# OMS_cup_wash_sucction.net
KiCad netlist of a schematic drawn in EAGLE
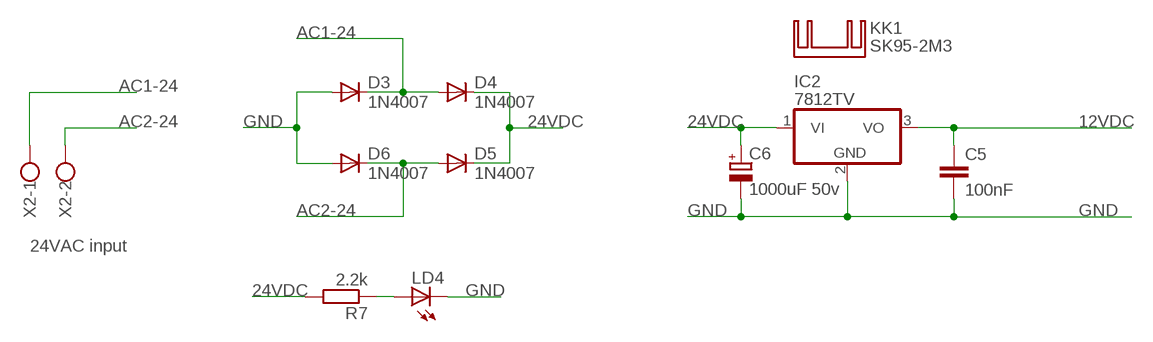
[diagram p0: schematic, sheet 1]
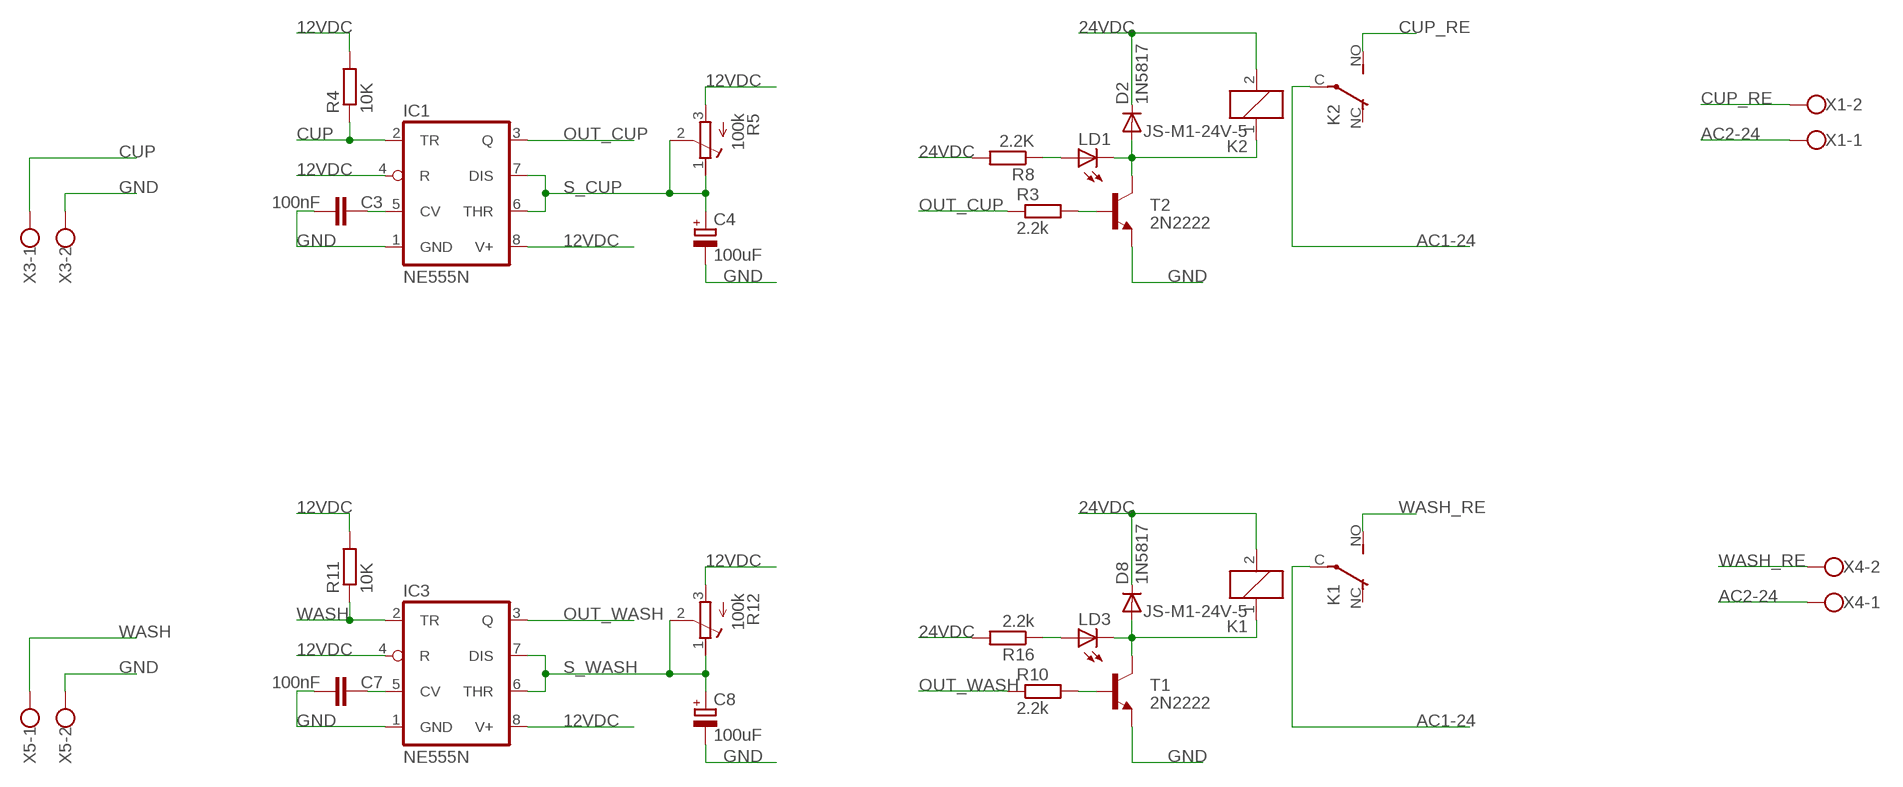
[diagram p1: schematic, sheet 2]
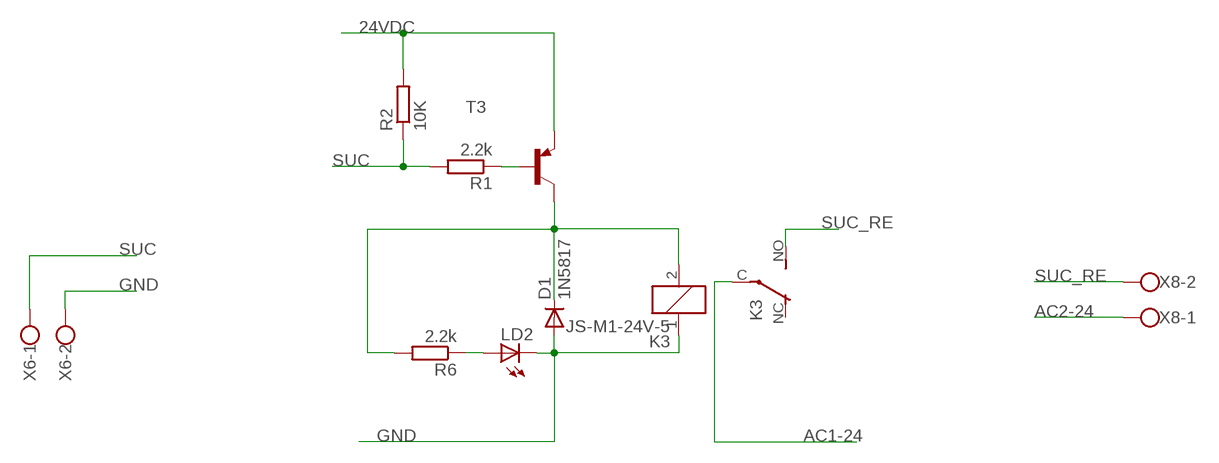
[diagram p2: schematic, sheet 3]

(export (version "E")
  (design (tool "Eeschema 10.0.6"))
  (components
    (comp (ref "D1")
      (value "1N5817")
      (footprint "eagle-import:DO41-10")
      (libsource (lib "eagle-import") (part "1N4004"))
    )
    (comp (ref "K3")
      (value "JS-M1-24V-5")
      (footprint "eagle-import:JS-M")
      (fields (field (name "MF") "FARNELL") (field (name "MPN") "JSM1-12V-5"))
      (libsource (lib "eagle-import") (part "JS-M1-12V-5"))
    )
    (comp (ref "LD2")
      (value "LED5MM")
      (footprint "eagle-import:LED5MM")
      (libsource (lib "eagle-import") (part "LED5MM"))
    )
    (comp (ref "R1")
      (value "2.2k")
      (footprint "eagle-import:0207_10")
      (libsource (lib "eagle-import") (part "R-EU_0207/10"))
    )
    (comp (ref "R2")
      (value "10K")
      (footprint "eagle-import:0207_10")
      (libsource (lib "eagle-import") (part "R-EU_0207/10"))
    )
    (comp (ref "R6")
      (value "2.2k")
      (footprint "eagle-import:0207_10")
      (libsource (lib "eagle-import") (part "R-EU_0207/10"))
    )
    (comp (ref "T3")
      (value "2N5401-PNP-TO92-EBC")
      (footprint "eagle-import:TO92-EBC")
      (libsource (lib "eagle-import") (part "-PNP-TO92-EBC2N5401"))
    )
    (comp (ref "X6")
      (value "W237-102")
      (footprint "eagle-import:W237-102")
      (libsource (lib "eagle-import") (part "W237-102"))
    )
    (comp (ref "X8")
      (value "W237-102")
      (footprint "eagle-import:W237-102")
      (libsource (lib "eagle-import") (part "W237-102"))
    )
    (comp (ref "C3")
      (value "100nF")
      (footprint "eagle-import:C050-025X075")
      (libsource (lib "eagle-import") (part "C-EU050-025X075"))
    )
    (comp (ref "C4")
      (value "100uF")
      (footprint "eagle-import:E3,5-8")
      (libsource (lib "eagle-import") (part "CPOL-EUE3.5-8"))
    )
    (comp (ref "C7")
      (value "100nF")
      (footprint "eagle-import:C050-025X075")
      (libsource (lib "eagle-import") (part "C-EU050-025X075"))
    )
    (comp (ref "C8")
      (value "100uF")
      (footprint "eagle-import:E3,5-8")
      (libsource (lib "eagle-import") (part "CPOL-EUE3.5-8"))
    )
    (comp (ref "D2")
      (value "1N5817")
      (footprint "eagle-import:DO41-10")
      (libsource (lib "eagle-import") (part "1N4004"))
    )
    (comp (ref "D8")
      (value "1N5817")
      (footprint "eagle-import:DO41-10")
      (libsource (lib "eagle-import") (part "1N4004"))
    )
    (comp (ref "IC1")
      (value "NE555N")
      (footprint "eagle-import:DIL08-ROUND")
      (libsource (lib "eagle-import") (part "555NNE"))
    )
    (comp (ref "IC3")
      (value "NE555N")
      (footprint "eagle-import:DIL08-ROUND")
      (libsource (lib "eagle-import") (part "555NNE"))
    )
    (comp (ref "K1")
      (value "JS-M1-24V-5")
      (footprint "eagle-import:JS-M")
      (fields (field (name "MF") "FARNELL") (field (name "MPN") "JSM1-12V-5"))
      (libsource (lib "eagle-import") (part "JS-M1-12V-5"))
    )
    (comp (ref "K2")
      (value "JS-M1-24V-5")
      (footprint "eagle-import:JS-M")
      (fields (field (name "MF") "FARNELL") (field (name "MPN") "JSM1-12V-5"))
      (libsource (lib "eagle-import") (part "JS-M1-12V-5"))
    )
    (comp (ref "LD1")
      (value "LED5MM")
      (footprint "eagle-import:LED5MM")
      (libsource (lib "eagle-import") (part "LED5MM"))
    )
    (comp (ref "LD3")
      (value "LED5MM")
      (footprint "eagle-import:LED5MM")
      (libsource (lib "eagle-import") (part "LED5MM"))
    )
    (comp (ref "R3")
      (value "2.2k")
      (footprint "eagle-import:0207_10")
      (libsource (lib "eagle-import") (part "R-EU_0207/10"))
    )
    (comp (ref "R4")
      (value "10K")
      (footprint "eagle-import:0207_10")
      (libsource (lib "eagle-import") (part "R-EU_0207/10"))
    )
    (comp (ref "R5")
      (value "100k")
      (footprint "eagle-import:RTRIMT93XA")
      (libsource (lib "eagle-import") (part "R-TRIMMT93XA"))
    )
    (comp (ref "R8")
      (value "2.2K")
      (footprint "eagle-import:0207_10")
      (libsource (lib "eagle-import") (part "R-EU_0207/10"))
    )
    (comp (ref "R10")
      (value "2.2k")
      (footprint "eagle-import:0207_10")
      (libsource (lib "eagle-import") (part "R-EU_0207/10"))
    )
    (comp (ref "R11")
      (value "10K")
      (footprint "eagle-import:0207_10")
      (libsource (lib "eagle-import") (part "R-EU_0207/10"))
    )
    (comp (ref "R12")
      (value "100k")
      (footprint "eagle-import:RTRIMT93XA")
      (libsource (lib "eagle-import") (part "R-TRIMMT93XA"))
    )
    (comp (ref "R16")
      (value "2.2k")
      (footprint "eagle-import:0207_10")
      (libsource (lib "eagle-import") (part "R-EU_0207/10"))
    )
    (comp (ref "T1")
      (value "2N2222")
      (footprint "eagle-import:TO92-EBC-OVAL")
      (libsource (lib "eagle-import") (part "2N2222"))
    )
    (comp (ref "T2")
      (value "2N2222")
      (footprint "eagle-import:TO92-EBC-OVAL")
      (libsource (lib "eagle-import") (part "2N2222"))
    )
    (comp (ref "X1")
      (value "W237-102")
      (footprint "eagle-import:W237-102")
      (libsource (lib "eagle-import") (part "W237-102"))
    )
    (comp (ref "X3")
      (value "W237-102")
      (footprint "eagle-import:W237-102")
      (libsource (lib "eagle-import") (part "W237-102"))
    )
    (comp (ref "X4")
      (value "W237-102")
      (footprint "eagle-import:W237-102")
      (libsource (lib "eagle-import") (part "W237-102"))
    )
    (comp (ref "X5")
      (value "W237-102")
      (footprint "eagle-import:W237-102")
      (libsource (lib "eagle-import") (part "W237-102"))
    )
    (comp (ref "C5")
      (value "100nF")
      (footprint "eagle-import:C050-025X075")
      (libsource (lib "eagle-import") (part "C-EU050-025X075"))
    )
    (comp (ref "C6")
      (value "1000uF 50v")
      (footprint "eagle-import:E5-13")
      (libsource (lib "eagle-import") (part "CPOL-EUE5-13"))
    )
    (comp (ref "D3")
      (value "1N4007")
      (footprint "eagle-import:DO41-10")
      (libsource (lib "eagle-import") (part "adafruit_420_1N4004"))
    )
    (comp (ref "D4")
      (value "1N4007")
      (footprint "eagle-import:DO41-10")
      (libsource (lib "eagle-import") (part "adafruit_420_1N4004"))
    )
    (comp (ref "D5")
      (value "1N4007")
      (footprint "eagle-import:DO41-10")
      (libsource (lib "eagle-import") (part "adafruit_420_1N4004"))
    )
    (comp (ref "D6")
      (value "1N4007")
      (footprint "eagle-import:DO41-10")
      (libsource (lib "eagle-import") (part "adafruit_420_1N4004"))
    )
    (comp (ref "IC2")
      (value "7812TV")
      (footprint "eagle-import:TO220V")
      (libsource (lib "eagle-import") (part "78TV12"))
    )
    (comp (ref "KK1")
      (value "SK95-2M3")
      (footprint "eagle-import:SK95-2M3")
      (libsource (lib "eagle-import") (part "SK95-2M3"))
    )
    (comp (ref "LD4")
      (value "LED5MM")
      (footprint "eagle-import:LED5MM")
      (libsource (lib "eagle-import") (part "LED5MM"))
    )
    (comp (ref "R7")
      (value "2.2k")
      (footprint "eagle-import:0207_10")
      (libsource (lib "eagle-import") (part "R-EU_0207/10"))
    )
    (comp (ref "X2")
      (value "W237-102")
      (footprint "eagle-import:W237-102")
      (libsource (lib "eagle-import") (part "W237-102"))
    )
  )
  (nets
    (net (code "1") (name "12VDC") (class "Default")
      (node (ref "C5") (pin "1") (pinfunction "1_1") (pintype "passive"))
      (node (ref "IC1") (pin "4") (pinfunction "R_4") (pintype "input"))
      (node (ref "IC1") (pin "8") (pinfunction "V+_8") (pintype "power_in"))
      (node (ref "IC2") (pin "3") (pinfunction "VO_3") (pintype "passive"))
      (node (ref "IC3") (pin "4") (pinfunction "R_4") (pintype "input"))
      (node (ref "IC3") (pin "8") (pinfunction "V+_8") (pintype "power_in"))
      (node (ref "R11") (pin "2") (pinfunction "2_2") (pintype "passive"))
      (node (ref "R12") (pin "3") (pinfunction "A_3") (pintype "passive"))
      (node (ref "R4") (pin "2") (pinfunction "2_2") (pintype "passive"))
      (node (ref "R5") (pin "3") (pinfunction "A_3") (pintype "passive"))
    )
    (net (code "2") (name "24VDC") (class "Default")
      (node (ref "C6") (pin "+") (pinfunction "+_+") (pintype "passive"))
      (node (ref "D2") (pin "C") (pinfunction "C_C") (pintype "passive"))
      (node (ref "D4") (pin "C") (pinfunction "C_C") (pintype "passive"))
      (node (ref "D5") (pin "C") (pinfunction "C_C") (pintype "passive"))
      (node (ref "D8") (pin "C") (pinfunction "C_C") (pintype "passive"))
      (node (ref "IC2") (pin "1") (pinfunction "VI_1") (pintype "input"))
      (node (ref "K1") (pin "2") (pinfunction "2_2") (pintype "passive"))
      (node (ref "K2") (pin "2") (pinfunction "2_2") (pintype "passive"))
      (node (ref "R16") (pin "2") (pinfunction "2_2") (pintype "passive"))
      (node (ref "R2") (pin "2") (pinfunction "2_2") (pintype "passive"))
      (node (ref "R7") (pin "2") (pinfunction "2_2") (pintype "passive"))
      (node (ref "R8") (pin "2") (pinfunction "2_2") (pintype "passive"))
      (node (ref "T3") (pin "E") (pinfunction "E_E") (pintype "passive"))
    )
    (net (code "3") (name "AC1-24") (class "Default")
      (node (ref "D3") (pin "C") (pinfunction "C_C") (pintype "passive"))
      (node (ref "D4") (pin "A") (pinfunction "A_A") (pintype "passive"))
      (node (ref "K1") (pin "C") (pinfunction "P_C") (pintype "passive"))
      (node (ref "K2") (pin "C") (pinfunction "P_C") (pintype "passive"))
      (node (ref "K3") (pin "C") (pinfunction "P_C") (pintype "passive"))
      (node (ref "X2") (pin "1") (pinfunction "KL_1") (pintype "passive"))
    )
    (net (code "4") (name "AC2-24") (class "Default")
      (node (ref "D5") (pin "A") (pinfunction "A_A") (pintype "passive"))
      (node (ref "D6") (pin "C") (pinfunction "C_C") (pintype "passive"))
      (node (ref "X1") (pin "1") (pinfunction "KL_1") (pintype "passive"))
      (node (ref "X2") (pin "2") (pinfunction "KL_2") (pintype "passive"))
      (node (ref "X4") (pin "1") (pinfunction "KL_1") (pintype "passive"))
      (node (ref "X8") (pin "1") (pinfunction "KL_1") (pintype "passive"))
    )
    (net (code "5") (name "CUP") (class "Default")
      (node (ref "IC1") (pin "2") (pinfunction "TR_2") (pintype "input"))
      (node (ref "R4") (pin "1") (pinfunction "1_1") (pintype "passive"))
      (node (ref "X3") (pin "1") (pinfunction "KL_1") (pintype "passive"))
    )
    (net (code "6") (name "CUP_RE") (class "Default")
      (node (ref "K2") (pin "NO") (pinfunction "S_NO") (pintype "passive"))
      (node (ref "X1") (pin "2") (pinfunction "KL_2") (pintype "passive"))
    )
    (net (code "7") (name "GND") (class "Default")
      (node (ref "C3") (pin "2") (pinfunction "2_2") (pintype "passive"))
      (node (ref "C4") (pin "-") (pinfunction "-_-") (pintype "passive"))
      (node (ref "C5") (pin "2") (pinfunction "2_2") (pintype "passive"))
      (node (ref "C6") (pin "-") (pinfunction "-_-") (pintype "passive"))
      (node (ref "C7") (pin "2") (pinfunction "2_2") (pintype "passive"))
      (node (ref "C8") (pin "-") (pinfunction "-_-") (pintype "passive"))
      (node (ref "D1") (pin "A") (pinfunction "A_A") (pintype "passive"))
      (node (ref "D3") (pin "A") (pinfunction "A_A") (pintype "passive"))
      (node (ref "D6") (pin "A") (pinfunction "A_A") (pintype "passive"))
      (node (ref "IC1") (pin "1") (pinfunction "GND_1") (pintype "power_in"))
      (node (ref "IC2") (pin "2") (pinfunction "GND_2") (pintype "passive"))
      (node (ref "IC3") (pin "1") (pinfunction "GND_1") (pintype "power_in"))
      (node (ref "K3") (pin "1") (pinfunction "1_1") (pintype "passive"))
      (node (ref "LD2") (pin "K") (pinfunction "C_K") (pintype "passive"))
      (node (ref "LD4") (pin "K") (pinfunction "C_K") (pintype "passive"))
      (node (ref "T1") (pin "E") (pinfunction "E_E") (pintype "passive"))
      (node (ref "T2") (pin "E") (pinfunction "E_E") (pintype "passive"))
      (node (ref "X3") (pin "2") (pinfunction "KL_2") (pintype "passive"))
      (node (ref "X5") (pin "2") (pinfunction "KL_2") (pintype "passive"))
      (node (ref "X6") (pin "2") (pinfunction "KL_2") (pintype "passive"))
    )
    (net (code "8") (name "Net-(D1-PadC)") (class "Default")
      (node (ref "D1") (pin "C") (pinfunction "C_C") (pintype "passive"))
      (node (ref "K3") (pin "2") (pinfunction "2_2") (pintype "passive"))
      (node (ref "R6") (pin "2") (pinfunction "2_2") (pintype "passive"))
      (node (ref "T3") (pin "C") (pinfunction "C_C") (pintype "passive"))
    )
    (net (code "9") (name "Net-(IC1-CV)") (class "Default")
      (node (ref "C3") (pin "1") (pinfunction "1_1") (pintype "passive"))
      (node (ref "IC1") (pin "5") (pinfunction "CV_5") (pintype "input"))
    )
    (net (code "10") (name "Net-(IC3-CV)") (class "Default")
      (node (ref "C7") (pin "1") (pinfunction "1_1") (pintype "passive"))
      (node (ref "IC3") (pin "5") (pinfunction "CV_5") (pintype "input"))
    )
    (net (code "11") (name "Net-(LD1-C)") (class "Default")
      (node (ref "D2") (pin "A") (pinfunction "A_A") (pintype "passive"))
      (node (ref "K2") (pin "1") (pinfunction "1_1") (pintype "passive"))
      (node (ref "LD1") (pin "K") (pinfunction "C_K") (pintype "passive"))
      (node (ref "T2") (pin "C") (pinfunction "C_C") (pintype "passive"))
    )
    (net (code "12") (name "Net-(LD1-PadA)") (class "Default")
      (node (ref "LD1") (pin "A") (pinfunction "A_A") (pintype "passive"))
      (node (ref "R8") (pin "1") (pinfunction "1_1") (pintype "passive"))
    )
    (net (code "13") (name "Net-(LD2-PadA)") (class "Default")
      (node (ref "LD2") (pin "A") (pinfunction "A_A") (pintype "passive"))
      (node (ref "R6") (pin "1") (pinfunction "1_1") (pintype "passive"))
    )
    (net (code "14") (name "Net-(LD3-C)") (class "Default")
      (node (ref "D8") (pin "A") (pinfunction "A_A") (pintype "passive"))
      (node (ref "K1") (pin "1") (pinfunction "1_1") (pintype "passive"))
      (node (ref "LD3") (pin "K") (pinfunction "C_K") (pintype "passive"))
      (node (ref "T1") (pin "C") (pinfunction "C_C") (pintype "passive"))
    )
    (net (code "15") (name "Net-(LD3-PadA)") (class "Default")
      (node (ref "LD3") (pin "A") (pinfunction "A_A") (pintype "passive"))
      (node (ref "R16") (pin "1") (pinfunction "1_1") (pintype "passive"))
    )
    (net (code "16") (name "Net-(LD4-PadA)") (class "Default")
      (node (ref "LD4") (pin "A") (pinfunction "A_A") (pintype "passive"))
      (node (ref "R7") (pin "1") (pinfunction "1_1") (pintype "passive"))
    )
    (net (code "17") (name "Net-(R1-Pad1)") (class "Default")
      (node (ref "R1") (pin "1") (pinfunction "1_1") (pintype "passive"))
      (node (ref "T3") (pin "B") (pinfunction "B_B") (pintype "passive"))
    )
    (net (code "18") (name "Net-(R3-Pad2)") (class "Default")
      (node (ref "R3") (pin "2") (pinfunction "2_2") (pintype "passive"))
      (node (ref "T2") (pin "B") (pinfunction "B_B") (pintype "passive"))
    )
    (net (code "19") (name "Net-(R10-Pad2)") (class "Default")
      (node (ref "R10") (pin "2") (pinfunction "2_2") (pintype "passive"))
      (node (ref "T1") (pin "B") (pinfunction "B_B") (pintype "passive"))
    )
    (net (code "20") (name "OUT_CUP") (class "Default")
      (node (ref "IC1") (pin "3") (pinfunction "Q_3") (pintype "output"))
      (node (ref "R3") (pin "1") (pinfunction "1_1") (pintype "passive"))
    )
    (net (code "21") (name "OUT_WASH") (class "Default")
      (node (ref "IC3") (pin "3") (pinfunction "Q_3") (pintype "output"))
      (node (ref "R10") (pin "1") (pinfunction "1_1") (pintype "passive"))
    )
    (net (code "22") (name "SUC") (class "Default")
      (node (ref "R1") (pin "2") (pinfunction "2_2") (pintype "passive"))
      (node (ref "R2") (pin "1") (pinfunction "1_1") (pintype "passive"))
      (node (ref "X6") (pin "1") (pinfunction "KL_1") (pintype "passive"))
    )
    (net (code "23") (name "SUC_RE") (class "Default")
      (node (ref "K3") (pin "NO") (pinfunction "S_NO") (pintype "passive"))
      (node (ref "X8") (pin "2") (pinfunction "KL_2") (pintype "passive"))
    )
    (net (code "24") (name "S_CUP") (class "Default")
      (node (ref "C4") (pin "+") (pinfunction "+_+") (pintype "passive"))
      (node (ref "IC1") (pin "6") (pinfunction "THR_6") (pintype "input"))
      (node (ref "IC1") (pin "7") (pinfunction "DIS_7") (pintype "input"))
      (node (ref "R5") (pin "1") (pinfunction "E_1") (pintype "passive"))
      (node (ref "R5") (pin "2") (pinfunction "S_2") (pintype "passive"))
    )
    (net (code "25") (name "S_WASH") (class "Default")
      (node (ref "C8") (pin "+") (pinfunction "+_+") (pintype "passive"))
      (node (ref "IC3") (pin "6") (pinfunction "THR_6") (pintype "input"))
      (node (ref "IC3") (pin "7") (pinfunction "DIS_7") (pintype "input"))
      (node (ref "R12") (pin "1") (pinfunction "E_1") (pintype "passive"))
      (node (ref "R12") (pin "2") (pinfunction "S_2") (pintype "passive"))
    )
    (net (code "26") (name "WASH") (class "Default")
      (node (ref "IC3") (pin "2") (pinfunction "TR_2") (pintype "input"))
      (node (ref "R11") (pin "1") (pinfunction "1_1") (pintype "passive"))
      (node (ref "X5") (pin "1") (pinfunction "KL_1") (pintype "passive"))
    )
    (net (code "27") (name "WASH_RE") (class "Default")
      (node (ref "K1") (pin "NO") (pinfunction "S_NO") (pintype "passive"))
      (node (ref "X4") (pin "2") (pinfunction "KL_2") (pintype "passive"))
    )
    (net (code "28") (name "unconnected-(K1B-O-PadNC)") (class "Default")
      (node (ref "K1") (pin "NC") (pinfunction "O_NC") (pintype "passive"))
    )
    (net (code "29") (name "unconnected-(K2B-O-PadNC)") (class "Default")
      (node (ref "K2") (pin "NC") (pinfunction "O_NC") (pintype "passive"))
    )
    (net (code "30") (name "unconnected-(K3B-O-PadNC)") (class "Default")
      (node (ref "K3") (pin "NC") (pinfunction "O_NC") (pintype "passive"))
    )
  )
)
